# RF.net
KiCad netlist of a schematic drawn in Altium Designer
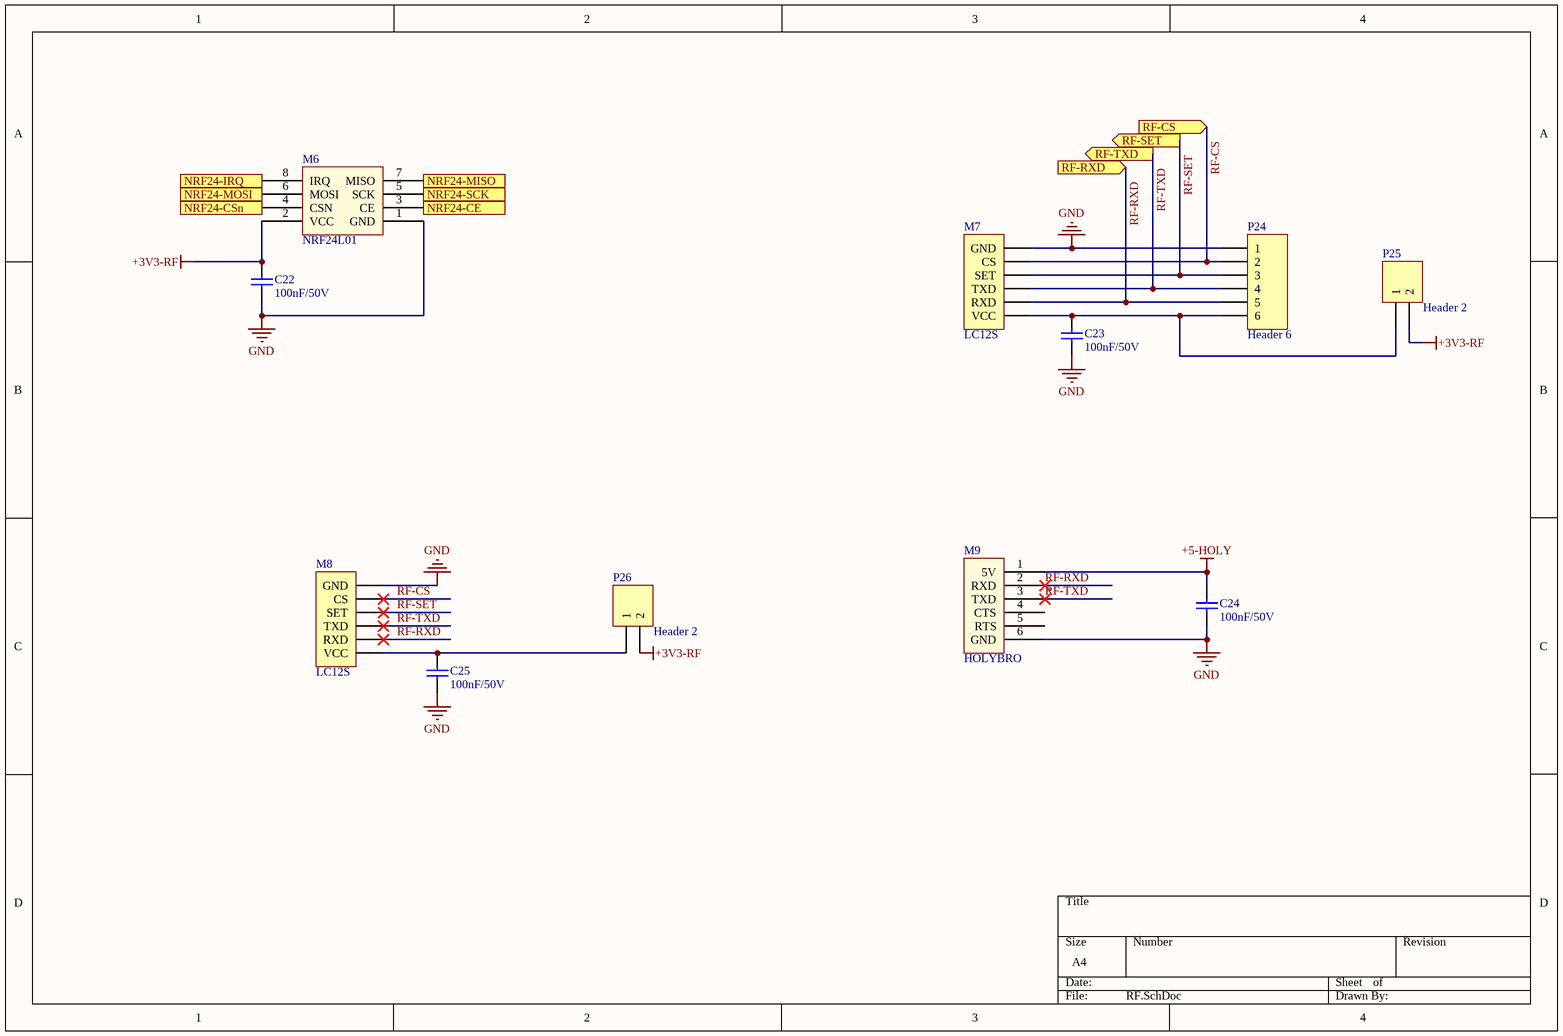
[diagram p0: RF.SchDoc]

(export (version "E")
  (design (tool "Eeschema 10.0.6"))
  (components
    (comp (ref "C22")
      (value "100nF/50V")
      (footprint "CAP-SM-0805")
      (description "CAP CER 0.1UF 50V Y5V 0805")
      (fields
        (field (name "MANUFACTURER") "Samsung Electro-Mechanics")
        (field (name "MANUFACTURER PART NUMBER") "CL21F104ZBCNNNC")
      )
      (libsource (lib "Capacitor") (part "Cap-100nF-50V-0805"))
    )
    (comp (ref "C23")
      (value "100nF/50V")
      (footprint "CAP-SM-0805")
      (description "CAP CER 0.1UF 50V Y5V 0805")
      (fields
        (field (name "MANUFACTURER") "Samsung Electro-Mechanics")
        (field (name "MANUFACTURER PART NUMBER") "CL21F104ZBCNNNC")
      )
      (libsource (lib "Capacitor") (part "Cap-100nF-50V-0805"))
    )
    (comp (ref "C24")
      (value "100nF/50V")
      (footprint "CAP-SM-0805")
      (description "CAP CER 0.1UF 50V Y5V 0805")
      (fields
        (field (name "MANUFACTURER") "Samsung Electro-Mechanics")
        (field (name "MANUFACTURER PART NUMBER") "CL21F104ZBCNNNC")
      )
      (libsource (lib "Capacitor") (part "Cap-100nF-50V-0805"))
    )
    (comp (ref "C25")
      (value "100nF/50V")
      (footprint "CAP-SM-0805")
      (description "CAP CER 0.1UF 50V Y5V 0805")
      (fields
        (field (name "MANUFACTURER") "Samsung Electro-Mechanics")
        (field (name "MANUFACTURER PART NUMBER") "CL21F104ZBCNNNC")
      )
      (libsource (lib "Capacitor") (part "Cap-100nF-50V-0805"))
    )
    (comp (ref "M6") (value "NRF24L01") (libsource (lib "MyLibrary1") (part "NRF24L01")))
    (comp (ref "M7") (value "LC12S") (libsource (lib "MyLibrary1") (part "LC12S")))
    (comp (ref "M8") (value "LC12S") (libsource (lib "MyLibrary1") (part "LC12S")))
    (comp (ref "M9") (value "HOLYBRO") (libsource (lib "MyLibrary1") (part "HOLYBRO")))
    (comp (ref "P24")
      (value "Header 6")
      (footprint "HDR1X6")
      (description "Header, 6-Pin")
      (fields (field (name "PUBLISHER") "Altium Limited"))
      (libsource (lib "Library2") (part "Header 6"))
    )
    (comp (ref "P25")
      (value "Header 2")
      (footprint "HDR1X2")
      (description "Header, 2-Pin")
      (fields (field (name "PUBLISHER") "Altium Limited"))
      (libsource (lib "Library2") (part "Header 2"))
    )
    (comp (ref "P26")
      (value "Header 2")
      (footprint "HDR1X2")
      (description "Header, 2-Pin")
      (fields (field (name "PUBLISHER") "Altium Limited"))
      (libsource (lib "Library2") (part "Header 2"))
    )
  )
  (nets
    (net (code "1") (name "+3V3-RF") (class "Default")
      (node (ref "C22") (pin "2") (pinfunction "2_2") (pintype "passive"))
      (node (ref "M6") (pin "2") (pinfunction "VCC_2") (pintype "passive"))
      (node (ref "P25") (pin "2") (pinfunction "2_2") (pintype "passive"))
      (node (ref "P26") (pin "2") (pinfunction "2_2") (pintype "passive"))
    )
    (net (code "2") (name "+5-HOLY") (class "Default")
      (node (ref "C24") (pin "2") (pinfunction "2_2") (pintype "passive"))
      (node (ref "M9") (pin "1") (pinfunction "5V_1") (pintype "passive"))
    )
    (net (code "3") (name "/NRF24-CE") (class "Default")
      (node (ref "M6") (pin "3") (pinfunction "CE_3") (pintype "passive"))
    )
    (net (code "4") (name "/NRF24-CSn") (class "Default")
      (node (ref "M6") (pin "4") (pinfunction "CSN_4") (pintype "passive"))
    )
    (net (code "5") (name "/NRF24-IRQ") (class "Default")
      (node (ref "M6") (pin "8") (pinfunction "IRQ_8") (pintype "passive"))
    )
    (net (code "6") (name "/NRF24-MISO") (class "Default")
      (node (ref "M6") (pin "7") (pinfunction "MISO_7") (pintype "passive"))
    )
    (net (code "7") (name "/NRF24-MOSI") (class "Default")
      (node (ref "M6") (pin "6") (pinfunction "MOSI_6") (pintype "passive"))
    )
    (net (code "8") (name "/NRF24-SCK") (class "Default")
      (node (ref "M6") (pin "5") (pinfunction "SCK_5") (pintype "passive"))
    )
    (net (code "9") (name "/RF-CS") (class "Default")
      (node (ref "M7") (pin "5") (pinfunction "CS_5") (pintype "passive"))
      (node (ref "M8") (pin "5") (pinfunction "CS_5") (pintype "passive"))
      (node (ref "P24") (pin "2") (pinfunction "2_2") (pintype "passive"))
    )
    (net (code "10") (name "/RF-RXD") (class "Default")
      (node (ref "M7") (pin "2") (pinfunction "RXD_2") (pintype "passive"))
      (node (ref "M8") (pin "2") (pinfunction "RXD_2") (pintype "passive"))
      (node (ref "M9") (pin "2") (pinfunction "RXD_2") (pintype "passive"))
      (node (ref "P24") (pin "5") (pinfunction "5_5") (pintype "passive"))
    )
    (net (code "11") (name "/RF-SET") (class "Default")
      (node (ref "M7") (pin "4") (pinfunction "SET_4") (pintype "power_in"))
      (node (ref "M8") (pin "4") (pinfunction "SET_4") (pintype "power_in"))
      (node (ref "P24") (pin "3") (pinfunction "3_3") (pintype "passive"))
    )
    (net (code "12") (name "/RF-TXD") (class "Default")
      (node (ref "M7") (pin "3") (pinfunction "TXD_3") (pintype "passive"))
      (node (ref "M8") (pin "3") (pinfunction "TXD_3") (pintype "passive"))
      (node (ref "M9") (pin "3") (pinfunction "TXD_3") (pintype "passive"))
      (node (ref "P24") (pin "4") (pinfunction "4_4") (pintype "passive"))
    )
    (net (code "13") (name "GND") (class "Default")
      (node (ref "C22") (pin "1") (pinfunction "1_1") (pintype "passive"))
      (node (ref "C23") (pin "1") (pinfunction "1_1") (pintype "passive"))
      (node (ref "C24") (pin "1") (pinfunction "1_1") (pintype "passive"))
      (node (ref "C25") (pin "1") (pinfunction "1_1") (pintype "passive"))
      (node (ref "M6") (pin "1") (pinfunction "GND_1") (pintype "passive"))
      (node (ref "M7") (pin "6") (pinfunction "GND_6") (pintype "power_in"))
      (node (ref "M8") (pin "6") (pinfunction "GND_6") (pintype "power_in"))
      (node (ref "M9") (pin "6") (pinfunction "GND_6") (pintype "passive"))
      (node (ref "P24") (pin "1") (pinfunction "1_1") (pintype "passive"))
    )
    (net (code "14") (name "Net-(M7-VCC)") (class "Default")
      (node (ref "C23") (pin "2") (pinfunction "2_2") (pintype "passive"))
      (node (ref "M7") (pin "1") (pinfunction "VCC_1") (pintype "power_in"))
      (node (ref "P24") (pin "6") (pinfunction "6_6") (pintype "passive"))
      (node (ref "P25") (pin "1") (pinfunction "1_1") (pintype "passive"))
    )
    (net (code "15") (name "Net-(M8-VCC)") (class "Default")
      (node (ref "C25") (pin "2") (pinfunction "2_2") (pintype "passive"))
      (node (ref "M8") (pin "1") (pinfunction "VCC_1") (pintype "power_in"))
      (node (ref "P26") (pin "1") (pinfunction "1_1") (pintype "passive"))
    )
    (net (code "16") (name "unconnected-(M9-CTS-Pad4)") (class "Default")
      (node (ref "M9") (pin "4") (pinfunction "CTS_4") (pintype "passive"))
    )
    (net (code "17") (name "unconnected-(M9-RTS-Pad5)") (class "Default")
      (node (ref "M9") (pin "5") (pinfunction "RTS_5") (pintype "passive"))
    )
  )
)
